# Driving.net
KiCad netlist of a schematic drawn in Altium Designer
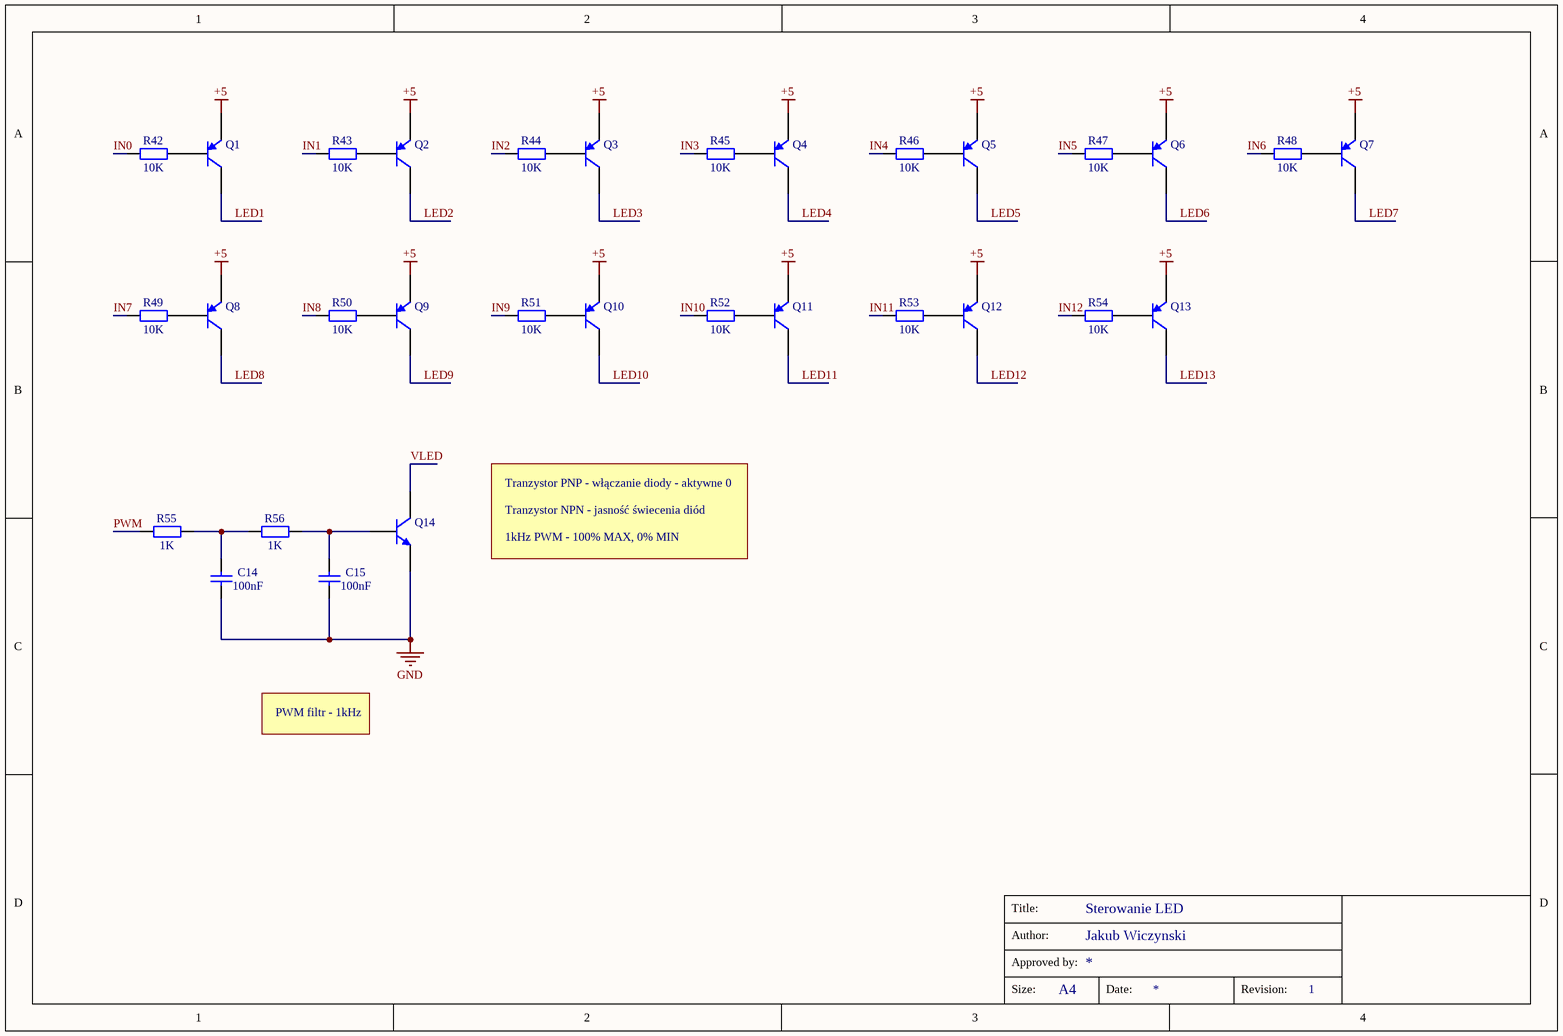
[diagram p0: Driving.SchDoc]

(export (version "E")
  (design (tool "Eeschema 10.0.6"))
  (components
    (comp (ref "C14")
      (value "100nF")
      (footprint "C1206")
      (fields
        (field (name "Comment") "http://www.tme.eu/pl/details/12061c104kat2a/kondensatory-mlcc-smd-1206/avx/")
        (field (name "PUBLISHER") "Altium Limited")
      )
      (libsource (lib "Miscellaneous Devices") (part "Cap"))
    )
    (comp (ref "C15")
      (value "100nF")
      (footprint "C1206")
      (fields
        (field (name "Comment") "http://www.tme.eu/pl/details/12061c104kat2a/kondensatory-mlcc-smd-1206/avx/")
        (field (name "PUBLISHER") "Altium Limited")
      )
      (libsource (lib "Miscellaneous Devices") (part "Cap"))
    )
    (comp (ref "Q1")
      (value "http://www.tme.eu/pl/details/bc856a/tranzystory-pnp-smd/nexperia/bc856a215/")
      (footprint "SOT-23B_N")
      (description "PNP 100mA")
      (fields (field (name "PUBLISHER") "Altium Limited"))
      (libsource (lib "Miscellaneous Devices") (part "PNP"))
    )
    (comp (ref "Q2")
      (value "http://www.tme.eu/pl/details/bc856a/tranzystory-pnp-smd/nexperia/bc856a215/")
      (footprint "SOT-23B_N")
      (description "PNP 100mA")
      (fields (field (name "PUBLISHER") "Altium Limited"))
      (libsource (lib "Miscellaneous Devices") (part "PNP"))
    )
    (comp (ref "Q3")
      (value "http://www.tme.eu/pl/details/bc856a/tranzystory-pnp-smd/nexperia/bc856a215/")
      (footprint "SOT-23B_N")
      (description "PNP 100mA")
      (fields (field (name "PUBLISHER") "Altium Limited"))
      (libsource (lib "Miscellaneous Devices") (part "PNP"))
    )
    (comp (ref "Q4")
      (value "http://www.tme.eu/pl/details/bc856a/tranzystory-pnp-smd/nexperia/bc856a215/")
      (footprint "SOT-23B_N")
      (description "PNP 100mA")
      (fields (field (name "PUBLISHER") "Altium Limited"))
      (libsource (lib "Miscellaneous Devices") (part "PNP"))
    )
    (comp (ref "Q5")
      (value "http://www.tme.eu/pl/details/bc856a/tranzystory-pnp-smd/nexperia/bc856a215/")
      (footprint "SOT-23B_N")
      (description "PNP 100mA")
      (fields (field (name "PUBLISHER") "Altium Limited"))
      (libsource (lib "Miscellaneous Devices") (part "PNP"))
    )
    (comp (ref "Q6")
      (value "http://www.tme.eu/pl/details/bc856a/tranzystory-pnp-smd/nexperia/bc856a215/")
      (footprint "SOT-23B_N")
      (description "PNP 100mA")
      (fields (field (name "PUBLISHER") "Altium Limited"))
      (libsource (lib "Miscellaneous Devices") (part "PNP"))
    )
    (comp (ref "Q7")
      (value "http://www.tme.eu/pl/details/bc856a/tranzystory-pnp-smd/nexperia/bc856a215/")
      (footprint "SOT-23B_N")
      (description "PNP 100mA")
      (fields (field (name "PUBLISHER") "Altium Limited"))
      (libsource (lib "Miscellaneous Devices") (part "PNP"))
    )
    (comp (ref "Q8")
      (value "http://www.tme.eu/pl/details/bc856a/tranzystory-pnp-smd/nexperia/bc856a215/")
      (footprint "SOT-23B_N")
      (description "PNP 100mA")
      (fields (field (name "PUBLISHER") "Altium Limited"))
      (libsource (lib "Miscellaneous Devices") (part "PNP"))
    )
    (comp (ref "Q9")
      (value "http://www.tme.eu/pl/details/bc856a/tranzystory-pnp-smd/nexperia/bc856a215/")
      (footprint "SOT-23B_N")
      (description "PNP 100mA")
      (fields (field (name "PUBLISHER") "Altium Limited"))
      (libsource (lib "Miscellaneous Devices") (part "PNP"))
    )
    (comp (ref "Q10")
      (value "http://www.tme.eu/pl/details/bc856a/tranzystory-pnp-smd/nexperia/bc856a215/")
      (footprint "SOT-23B_N")
      (description "PNP 100mA")
      (fields (field (name "PUBLISHER") "Altium Limited"))
      (libsource (lib "Miscellaneous Devices") (part "PNP"))
    )
    (comp (ref "Q11")
      (value "http://www.tme.eu/pl/details/bc856a/tranzystory-pnp-smd/nexperia/bc856a215/")
      (footprint "SOT-23B_N")
      (description "PNP 100mA")
      (fields (field (name "PUBLISHER") "Altium Limited"))
      (libsource (lib "Miscellaneous Devices") (part "PNP"))
    )
    (comp (ref "Q12")
      (value "http://www.tme.eu/pl/details/bc856a/tranzystory-pnp-smd/nexperia/bc856a215/")
      (footprint "SOT-23B_N")
      (description "PNP 100mA")
      (fields (field (name "PUBLISHER") "Altium Limited"))
      (libsource (lib "Miscellaneous Devices") (part "PNP"))
    )
    (comp (ref "Q13")
      (value "http://www.tme.eu/pl/details/bc856a/tranzystory-pnp-smd/nexperia/bc856a215/")
      (footprint "SOT-23B_N")
      (description "PNP 100mA")
      (fields (field (name "PUBLISHER") "Altium Limited"))
      (libsource (lib "Miscellaneous Devices") (part "PNP"))
    )
    (comp (ref "Q14")
      (value "http://www.tme.eu/pl/details/bc817-16.215/tranzystory-npn-smd/nexperia/")
      (footprint "SOT-23B_N")
      (description "NPN 500mA")
      (fields (field (name "PUBLISHER") "Altium Limited"))
      (libsource (lib "Miscellaneous Devices") (part "NPN"))
    )
    (comp (ref "R42")
      (value "10K")
      (footprint "C1206")
      (fields
        (field (name "Comment") "http://www.tme.eu/pl/details/crcw120610k0jntabc/rezystory-smd-1206/vishay/")
        (field (name "PUBLISHER") "Altium Limited")
      )
      (libsource (lib "Miscellaneous Devices") (part "Res2"))
    )
    (comp (ref "R43")
      (value "10K")
      (footprint "C1206")
      (fields
        (field (name "Comment") "http://www.tme.eu/pl/details/crcw120610k0jntabc/rezystory-smd-1206/vishay/")
        (field (name "PUBLISHER") "Altium Limited")
      )
      (libsource (lib "Miscellaneous Devices") (part "Res2"))
    )
    (comp (ref "R44")
      (value "10K")
      (footprint "C1206")
      (fields
        (field (name "Comment") "http://www.tme.eu/pl/details/crcw120610k0jntabc/rezystory-smd-1206/vishay/")
        (field (name "PUBLISHER") "Altium Limited")
      )
      (libsource (lib "Miscellaneous Devices") (part "Res2"))
    )
    (comp (ref "R45")
      (value "10K")
      (footprint "C1206")
      (fields
        (field (name "Comment") "http://www.tme.eu/pl/details/crcw120610k0jntabc/rezystory-smd-1206/vishay/")
        (field (name "PUBLISHER") "Altium Limited")
      )
      (libsource (lib "Miscellaneous Devices") (part "Res2"))
    )
    (comp (ref "R46")
      (value "10K")
      (footprint "C1206")
      (fields
        (field (name "Comment") "http://www.tme.eu/pl/details/crcw120610k0jntabc/rezystory-smd-1206/vishay/")
        (field (name "PUBLISHER") "Altium Limited")
      )
      (libsource (lib "Miscellaneous Devices") (part "Res2"))
    )
    (comp (ref "R47")
      (value "10K")
      (footprint "C1206")
      (fields
        (field (name "Comment") "http://www.tme.eu/pl/details/crcw120610k0jntabc/rezystory-smd-1206/vishay/")
        (field (name "PUBLISHER") "Altium Limited")
      )
      (libsource (lib "Miscellaneous Devices") (part "Res2"))
    )
    (comp (ref "R48")
      (value "10K")
      (footprint "C1206")
      (fields
        (field (name "Comment") "http://www.tme.eu/pl/details/crcw120610k0jntabc/rezystory-smd-1206/vishay/")
        (field (name "PUBLISHER") "Altium Limited")
      )
      (libsource (lib "Miscellaneous Devices") (part "Res2"))
    )
    (comp (ref "R49")
      (value "10K")
      (footprint "C1206")
      (fields
        (field (name "Comment") "http://www.tme.eu/pl/details/crcw120610k0jntabc/rezystory-smd-1206/vishay/")
        (field (name "PUBLISHER") "Altium Limited")
      )
      (libsource (lib "Miscellaneous Devices") (part "Res2"))
    )
    (comp (ref "R50")
      (value "10K")
      (footprint "C1206")
      (fields
        (field (name "Comment") "http://www.tme.eu/pl/details/crcw120610k0jntabc/rezystory-smd-1206/vishay/")
        (field (name "PUBLISHER") "Altium Limited")
      )
      (libsource (lib "Miscellaneous Devices") (part "Res2"))
    )
    (comp (ref "R51")
      (value "10K")
      (footprint "C1206")
      (fields
        (field (name "Comment") "http://www.tme.eu/pl/details/crcw120610k0jntabc/rezystory-smd-1206/vishay/")
        (field (name "PUBLISHER") "Altium Limited")
      )
      (libsource (lib "Miscellaneous Devices") (part "Res2"))
    )
    (comp (ref "R52")
      (value "10K")
      (footprint "C1206")
      (fields
        (field (name "Comment") "http://www.tme.eu/pl/details/crcw120610k0jntabc/rezystory-smd-1206/vishay/")
        (field (name "PUBLISHER") "Altium Limited")
      )
      (libsource (lib "Miscellaneous Devices") (part "Res2"))
    )
    (comp (ref "R53")
      (value "10K")
      (footprint "C1206")
      (fields
        (field (name "Comment") "http://www.tme.eu/pl/details/crcw120610k0jntabc/rezystory-smd-1206/vishay/")
        (field (name "PUBLISHER") "Altium Limited")
      )
      (libsource (lib "Miscellaneous Devices") (part "Res2"))
    )
    (comp (ref "R54")
      (value "10K")
      (footprint "C1206")
      (fields
        (field (name "Comment") "http://www.tme.eu/pl/details/crcw120610k0jntabc/rezystory-smd-1206/vishay/")
        (field (name "PUBLISHER") "Altium Limited")
      )
      (libsource (lib "Miscellaneous Devices") (part "Res2"))
    )
    (comp (ref "R55")
      (value "1K")
      (footprint "C1206")
      (fields
        (field (name "Comment") "http://www.tme.eu/pl/details/crcw12061k00fkea/rezystory-smd-1206/vishay/")
        (field (name "PUBLISHER") "Altium Limited")
      )
      (libsource (lib "Miscellaneous Devices") (part "Res2"))
    )
    (comp (ref "R56")
      (value "1K")
      (footprint "C1206")
      (fields
        (field (name "Comment") "http://www.tme.eu/pl/details/crcw12061k00fkea/rezystory-smd-1206/vishay/")
        (field (name "PUBLISHER") "Altium Limited")
      )
      (libsource (lib "Miscellaneous Devices") (part "Res2"))
    )
  )
  (nets
    (net (code "1") (name "+5") (class "Default")
      (node (ref "Q1") (pin "3") (pinfunction "E_3") (pintype "passive"))
      (node (ref "Q10") (pin "3") (pinfunction "E_3") (pintype "passive"))
      (node (ref "Q11") (pin "3") (pinfunction "E_3") (pintype "passive"))
      (node (ref "Q12") (pin "3") (pinfunction "E_3") (pintype "passive"))
      (node (ref "Q13") (pin "3") (pinfunction "E_3") (pintype "passive"))
      (node (ref "Q2") (pin "3") (pinfunction "E_3") (pintype "passive"))
      (node (ref "Q3") (pin "3") (pinfunction "E_3") (pintype "passive"))
      (node (ref "Q4") (pin "3") (pinfunction "E_3") (pintype "passive"))
      (node (ref "Q5") (pin "3") (pinfunction "E_3") (pintype "passive"))
      (node (ref "Q6") (pin "3") (pinfunction "E_3") (pintype "passive"))
      (node (ref "Q7") (pin "3") (pinfunction "E_3") (pintype "passive"))
      (node (ref "Q8") (pin "3") (pinfunction "E_3") (pintype "passive"))
      (node (ref "Q9") (pin "3") (pinfunction "E_3") (pintype "passive"))
    )
    (net (code "2") (name "/IN0") (class "Default")
      (node (ref "R42") (pin "1") (pinfunction "1_1") (pintype "passive"))
    )
    (net (code "3") (name "/IN1") (class "Default")
      (node (ref "R43") (pin "1") (pinfunction "1_1") (pintype "passive"))
    )
    (net (code "4") (name "/IN2") (class "Default")
      (node (ref "R44") (pin "1") (pinfunction "1_1") (pintype "passive"))
    )
    (net (code "5") (name "/IN3") (class "Default")
      (node (ref "R45") (pin "1") (pinfunction "1_1") (pintype "passive"))
    )
    (net (code "6") (name "/IN4") (class "Default")
      (node (ref "R46") (pin "1") (pinfunction "1_1") (pintype "passive"))
    )
    (net (code "7") (name "/IN5") (class "Default")
      (node (ref "R47") (pin "1") (pinfunction "1_1") (pintype "passive"))
    )
    (net (code "8") (name "/IN6") (class "Default")
      (node (ref "R48") (pin "1") (pinfunction "1_1") (pintype "passive"))
    )
    (net (code "9") (name "/IN7") (class "Default")
      (node (ref "R49") (pin "1") (pinfunction "1_1") (pintype "passive"))
    )
    (net (code "10") (name "/IN8") (class "Default")
      (node (ref "R50") (pin "1") (pinfunction "1_1") (pintype "passive"))
    )
    (net (code "11") (name "/IN9") (class "Default")
      (node (ref "R51") (pin "1") (pinfunction "1_1") (pintype "passive"))
    )
    (net (code "12") (name "/IN10") (class "Default")
      (node (ref "R52") (pin "1") (pinfunction "1_1") (pintype "passive"))
    )
    (net (code "13") (name "/IN11") (class "Default")
      (node (ref "R53") (pin "1") (pinfunction "1_1") (pintype "passive"))
    )
    (net (code "14") (name "/IN12") (class "Default")
      (node (ref "R54") (pin "1") (pinfunction "1_1") (pintype "passive"))
    )
    (net (code "15") (name "/LED1") (class "Default")
      (node (ref "Q1") (pin "1") (pinfunction "C_1") (pintype "passive"))
    )
    (net (code "16") (name "/LED2") (class "Default")
      (node (ref "Q2") (pin "1") (pinfunction "C_1") (pintype "passive"))
    )
    (net (code "17") (name "/LED3") (class "Default")
      (node (ref "Q3") (pin "1") (pinfunction "C_1") (pintype "passive"))
    )
    (net (code "18") (name "/LED4") (class "Default")
      (node (ref "Q4") (pin "1") (pinfunction "C_1") (pintype "passive"))
    )
    (net (code "19") (name "/LED5") (class "Default")
      (node (ref "Q5") (pin "1") (pinfunction "C_1") (pintype "passive"))
    )
    (net (code "20") (name "/LED6") (class "Default")
      (node (ref "Q6") (pin "1") (pinfunction "C_1") (pintype "passive"))
    )
    (net (code "21") (name "/LED7") (class "Default")
      (node (ref "Q7") (pin "1") (pinfunction "C_1") (pintype "passive"))
    )
    (net (code "22") (name "/LED8") (class "Default")
      (node (ref "Q8") (pin "1") (pinfunction "C_1") (pintype "passive"))
    )
    (net (code "23") (name "/LED9") (class "Default")
      (node (ref "Q9") (pin "1") (pinfunction "C_1") (pintype "passive"))
    )
    (net (code "24") (name "/LED10") (class "Default")
      (node (ref "Q10") (pin "1") (pinfunction "C_1") (pintype "passive"))
    )
    (net (code "25") (name "/LED11") (class "Default")
      (node (ref "Q11") (pin "1") (pinfunction "C_1") (pintype "passive"))
    )
    (net (code "26") (name "/LED12") (class "Default")
      (node (ref "Q12") (pin "1") (pinfunction "C_1") (pintype "passive"))
    )
    (net (code "27") (name "/LED13") (class "Default")
      (node (ref "Q13") (pin "1") (pinfunction "C_1") (pintype "passive"))
    )
    (net (code "28") (name "/PWM") (class "Default")
      (node (ref "R55") (pin "1") (pinfunction "1_1") (pintype "passive"))
    )
    (net (code "29") (name "/VLED") (class "Default")
      (node (ref "Q14") (pin "1") (pinfunction "C_1") (pintype "passive"))
    )
    (net (code "30") (name "GND") (class "Default")
      (node (ref "C14") (pin "1") (pinfunction "1_1") (pintype "passive"))
      (node (ref "C15") (pin "1") (pinfunction "1_1") (pintype "passive"))
      (node (ref "Q14") (pin "3") (pinfunction "E_3") (pintype "passive"))
    )
    (net (code "31") (name "Net-(C14-Pad2)") (class "Default")
      (node (ref "C14") (pin "2") (pinfunction "2_2") (pintype "passive"))
      (node (ref "R55") (pin "2") (pinfunction "2_2") (pintype "passive"))
      (node (ref "R56") (pin "1") (pinfunction "1_1") (pintype "passive"))
    )
    (net (code "32") (name "Net-(Q1-B)") (class "Default")
      (node (ref "Q1") (pin "2") (pinfunction "B_2") (pintype "passive"))
      (node (ref "R42") (pin "2") (pinfunction "2_2") (pintype "passive"))
    )
    (net (code "33") (name "Net-(Q2-B)") (class "Default")
      (node (ref "Q2") (pin "2") (pinfunction "B_2") (pintype "passive"))
      (node (ref "R43") (pin "2") (pinfunction "2_2") (pintype "passive"))
    )
    (net (code "34") (name "Net-(Q3-B)") (class "Default")
      (node (ref "Q3") (pin "2") (pinfunction "B_2") (pintype "passive"))
      (node (ref "R44") (pin "2") (pinfunction "2_2") (pintype "passive"))
    )
    (net (code "35") (name "Net-(Q4-B)") (class "Default")
      (node (ref "Q4") (pin "2") (pinfunction "B_2") (pintype "passive"))
      (node (ref "R45") (pin "2") (pinfunction "2_2") (pintype "passive"))
    )
    (net (code "36") (name "Net-(Q5-B)") (class "Default")
      (node (ref "Q5") (pin "2") (pinfunction "B_2") (pintype "passive"))
      (node (ref "R46") (pin "2") (pinfunction "2_2") (pintype "passive"))
    )
    (net (code "37") (name "Net-(Q6-B)") (class "Default")
      (node (ref "Q6") (pin "2") (pinfunction "B_2") (pintype "passive"))
      (node (ref "R47") (pin "2") (pinfunction "2_2") (pintype "passive"))
    )
    (net (code "38") (name "Net-(Q7-B)") (class "Default")
      (node (ref "Q7") (pin "2") (pinfunction "B_2") (pintype "passive"))
      (node (ref "R48") (pin "2") (pinfunction "2_2") (pintype "passive"))
    )
    (net (code "39") (name "Net-(Q8-B)") (class "Default")
      (node (ref "Q8") (pin "2") (pinfunction "B_2") (pintype "passive"))
      (node (ref "R49") (pin "2") (pinfunction "2_2") (pintype "passive"))
    )
    (net (code "40") (name "Net-(Q9-B)") (class "Default")
      (node (ref "Q9") (pin "2") (pinfunction "B_2") (pintype "passive"))
      (node (ref "R50") (pin "2") (pinfunction "2_2") (pintype "passive"))
    )
    (net (code "41") (name "Net-(Q10-B)") (class "Default")
      (node (ref "Q10") (pin "2") (pinfunction "B_2") (pintype "passive"))
      (node (ref "R51") (pin "2") (pinfunction "2_2") (pintype "passive"))
    )
    (net (code "42") (name "Net-(Q11-B)") (class "Default")
      (node (ref "Q11") (pin "2") (pinfunction "B_2") (pintype "passive"))
      (node (ref "R52") (pin "2") (pinfunction "2_2") (pintype "passive"))
    )
    (net (code "43") (name "Net-(Q12-B)") (class "Default")
      (node (ref "Q12") (pin "2") (pinfunction "B_2") (pintype "passive"))
      (node (ref "R53") (pin "2") (pinfunction "2_2") (pintype "passive"))
    )
    (net (code "44") (name "Net-(Q13-B)") (class "Default")
      (node (ref "Q13") (pin "2") (pinfunction "B_2") (pintype "passive"))
      (node (ref "R54") (pin "2") (pinfunction "2_2") (pintype "passive"))
    )
    (net (code "45") (name "Net-(Q14-B)") (class "Default")
      (node (ref "C15") (pin "2") (pinfunction "2_2") (pintype "passive"))
      (node (ref "Q14") (pin "2") (pinfunction "B_2") (pintype "passive"))
      (node (ref "R56") (pin "2") (pinfunction "2_2") (pintype "passive"))
    )
  )
)
